# Power_Supply.net
KiCad netlist of a schematic drawn in Altium Designer
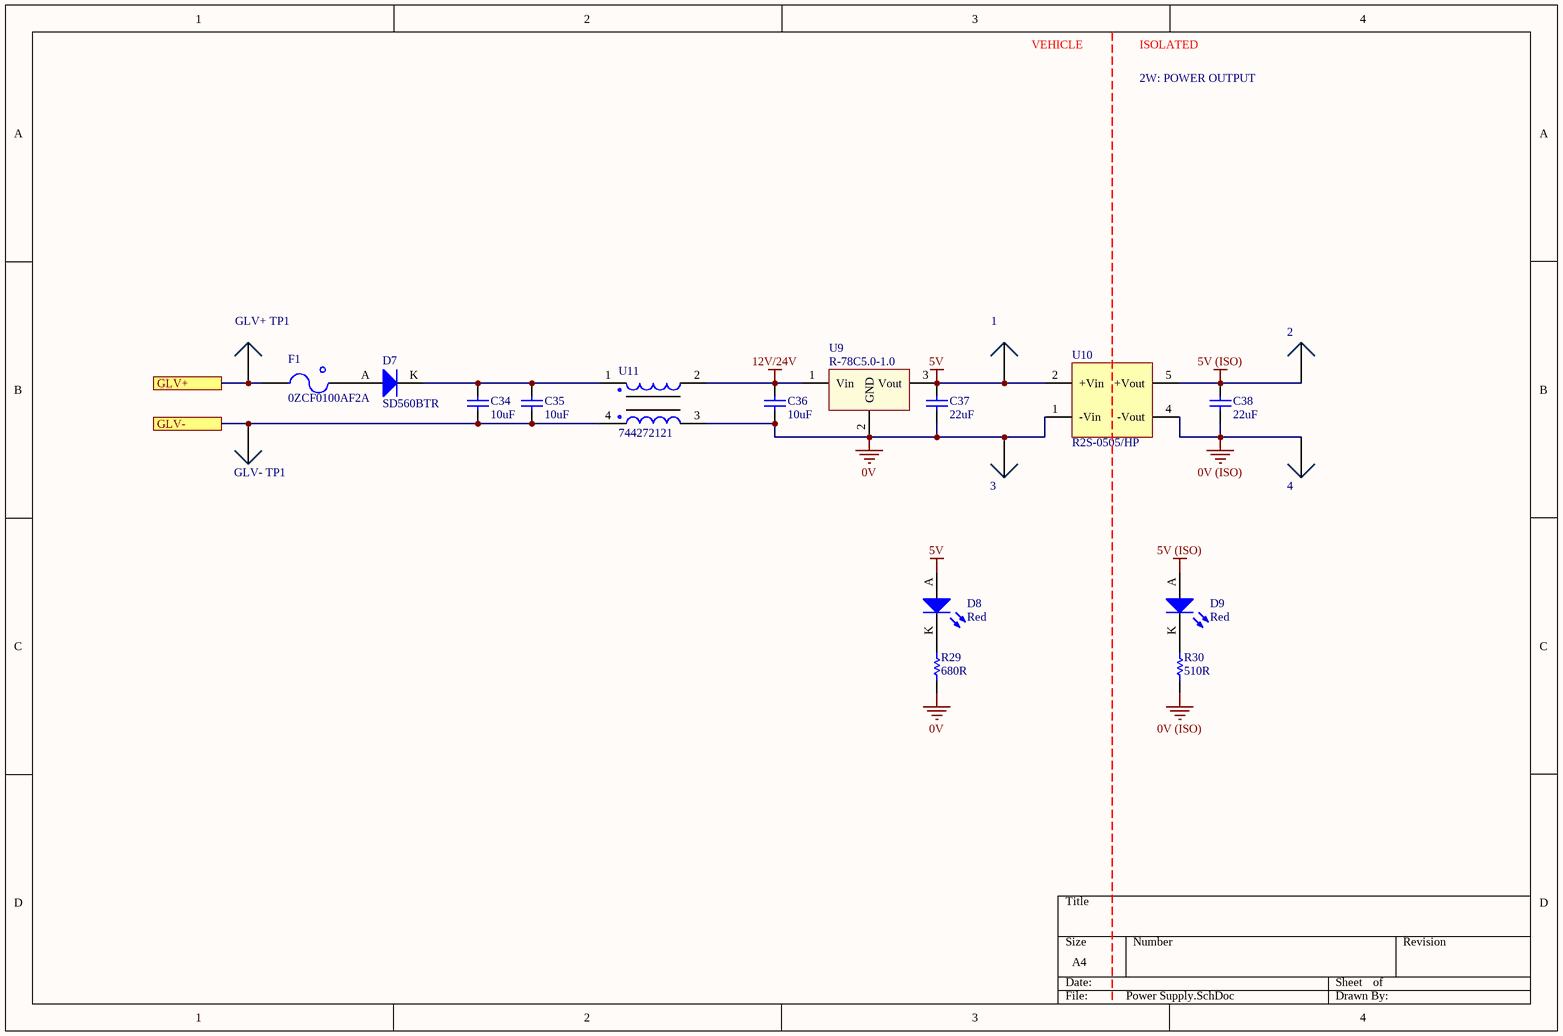
[diagram p0: Power Supply.SchDoc]

(export (version "E")
  (design (tool "Eeschema 10.0.6"))
  (components
    (comp (ref "1")
      (value "0mm")
      (footprint "SMD Test Point")
      (fields (field (name "PART NUMBER") "SMD Test Point") (field (name "CONTACT") "NA"))
      (libsource (lib "ts_20-standard-connectors") (part "Test Point"))
    )
    (comp (ref "2")
      (value "0mm")
      (footprint "SMD Test Point")
      (fields (field (name "PART NUMBER") "SMD Test Point") (field (name "CONTACT") "NA"))
      (libsource (lib "ts_20-standard-connectors") (part "Test Point"))
    )
    (comp (ref "3")
      (value "0mm")
      (footprint "SMD Test Point")
      (fields (field (name "PART NUMBER") "SMD Test Point") (field (name "CONTACT") "NA"))
      (libsource (lib "ts_20-standard-connectors") (part "Test Point"))
    )
    (comp (ref "4")
      (value "0mm")
      (footprint "SMD Test Point")
      (fields (field (name "PART NUMBER") "SMD Test Point") (field (name "CONTACT") "NA"))
      (libsource (lib "ts_20-standard-connectors") (part "Test Point"))
    )
    (comp (ref "C34")
      (value "10uF")
      (footprint "0805")
      (fields
        (field (name "PART NUMBER") "GRM21BR6YA106KE43L")
        (field (name "TOLERANCE") "10%")
        (field (name "MANUFACTURER") "muRata")
      )
      (libsource (lib "ts_20-standard-library") (part "Capacitor"))
    )
    (comp (ref "C35")
      (value "10uF")
      (footprint "0805")
      (fields
        (field (name "PART NUMBER") "GRM21BR6YA106KE43L")
        (field (name "TOLERANCE") "10%")
        (field (name "MANUFACTURER") "muRata")
      )
      (libsource (lib "ts_20-standard-library") (part "Capacitor"))
    )
    (comp (ref "C36")
      (value "10uF")
      (footprint "0805")
      (fields
        (field (name "PART NUMBER") "GRM21BR6YA106KE43L")
        (field (name "TOLERANCE") "10%")
        (field (name "MANUFACTURER") "muRata")
      )
      (libsource (lib "ts_20-standard-library") (part "Capacitor"))
    )
    (comp (ref "C37")
      (value "22uF")
      (footprint "1206")
      (fields
        (field (name "PART NUMBER") "CC1206MKX5R7BB226")
        (field (name "TOLERANCE") "20%")
        (field (name "MANUFACTURER") "YAGEO")
      )
      (libsource (lib "ts_20-standard-library") (part "Capacitor"))
    )
    (comp (ref "C38")
      (value "22uF")
      (footprint "1206")
      (fields
        (field (name "PART NUMBER") "CC1206MKX5R7BB226")
        (field (name "TOLERANCE") "20%")
        (field (name "MANUFACTURER") "YAGEO")
      )
      (libsource (lib "ts_20-standard-library") (part "Capacitor"))
    )
    (comp (ref "D7")
      (value "SD560BTR")
      (footprint "SMB Diode")
      (description "1.2V_F 600V 5A SMB")
      (fields
        (field (name "MANUFACTURER") "SMC Diode Solutions")
        (field (name "DIGIKEY PART NUMBER") "1655-1530-2-ND")
      )
      (libsource (lib "ts_20-standard-library") (part "Diode"))
    )
    (comp (ref "D8")
      (value "Red")
      (footprint "0805 LED")
      (description "Red LED Indication - Discrete 1.75V 0805 (2012 Metric)")
      (fields (field (name "PART NUMBER") "SML-210LTT86") (field (name "MANUFACTURER") "ROHM Semiconductor"))
      (libsource (lib "ts_20-standard-library") (part "LED"))
    )
    (comp (ref "D9")
      (value "Red")
      (footprint "0805 LED")
      (description "Red LED Indication - Discrete 1.75V 0805 (2012 Metric)")
      (fields (field (name "PART NUMBER") "SML-210LTT86") (field (name "MANUFACTURER") "ROHM Semiconductor"))
      (libsource (lib "ts_20-standard-library") (part "LED"))
    )
    (comp (ref "F1")
      (value "0ZCF0100AF2A")
      (footprint "2920")
      (description "PTC RESET FUSE 60V 1A 292")
      (fields
        (field (name "MANUFACTURER") "Littelfuse Inc.")
        (field (name "DIGIKEY PART NUMBER") "507-2070-1-ND")
      )
      (libsource (lib "ts_20-standard-library") (part "PTC Fuse"))
    )
    (comp (ref "GLV+ TP1")
      (value "0mm")
      (footprint "SMD Test Point")
      (fields (field (name "PART NUMBER") "SMD Test Point") (field (name "CONTACT") "NA"))
      (libsource (lib "ts_20-standard-connectors") (part "Test Point"))
    )
    (comp (ref "GLV- TP1")
      (value "0mm")
      (footprint "SMD Test Point")
      (fields (field (name "PART NUMBER") "SMD Test Point") (field (name "CONTACT") "NA"))
      (libsource (lib "ts_20-standard-connectors") (part "Test Point"))
    )
    (comp (ref "R29")
      (value "680R")
      (footprint "0805")
      (fields
        (field (name "PART NUMBER") "RC0805FR07680RL")
        (field (name "MANUFACTURER") "YAGEO")
        (field (name "TOLERANCE") "0.01")
      )
      (libsource (lib "ts_20-standard-library") (part "Resistor"))
    )
    (comp (ref "R30")
      (value "510R")
      (footprint "0805")
      (fields
        (field (name "PART NUMBER") "RC0805FR07510RL")
        (field (name "MANUFACTURER") "YAGEO")
        (field (name "TOLERANCE") "0.01")
      )
      (libsource (lib "ts_20-standard-library") (part "Resistor"))
    )
    (comp (ref "U9")
      (value "R-78C5.0-1.0")
      (footprint "RECOM 3-SIP")
      (description "CONV DC/DC 1A 5V OUT SIP VERT")
      (fields (field (name "MANUFACTURER") "Recom") (field (name "DIGIKEY PART NUMBER") "945-1395-5-ND"))
      (libsource (lib "ts_20-standard-library") (part "R-78C5.0-1.0"))
    )
    (comp (ref "U10")
      (value "R2S-0505/HP")
      (footprint "RECOM 8-SMD (5 Pin)")
      (description "Isolated Module DC DC Converter 1 Output 3.3V 606mA 4.5V - 5.5V Input")
      (fields (field (name "MANUFACTURER") "Recom") (field (name "DIGIKEY PART NUMBER") "945-1764-5-ND"))
      (libsource (lib "ts_20-standard-library") (part "R2S-0505/HP"))
    )
    (comp (ref "U11")
      (value "744272121")
      (footprint "INDC3216")
      (description "120µH @ 100kHz 2 Line Common Mode Choke Surface Mount 460 Ohms @ 30MHz 2.5A DCR 25mOhm")
      (fields
        (field (name "MANUFACTURER") "Wurth Electronics Inc")
        (field (name "DIGIKEY PART NUMBER") "732-1489-1-ND")
      )
      (libsource (lib "ts_20-standard-library") (part "744272121"))
    )
  )
  (nets
    (net (code "1") (name "/GLV+") (class "Default")
      (node (ref "F1") (pin "1") (pinfunction "1_1") (pintype "passive"))
      (node (ref "GLV+ TP1") (pin "1") (pinfunction "1_1") (pintype "passive"))
    )
    (net (code "2") (name "/GLV-") (class "Default")
      (node (ref "C34") (pin "1") (pinfunction "1_1") (pintype "passive"))
      (node (ref "C35") (pin "1") (pinfunction "1_1") (pintype "passive"))
      (node (ref "GLV- TP1") (pin "1") (pinfunction "1_1") (pintype "passive"))
      (node (ref "U11") (pin "4") (pinfunction "4_4") (pintype "passive"))
    )
    (net (code "3") (name "0V") (class "Default")
      (node (ref "3") (pin "1") (pinfunction "1_1") (pintype "passive"))
      (node (ref "C36") (pin "1") (pinfunction "1_1") (pintype "passive"))
      (node (ref "C37") (pin "1") (pinfunction "1_1") (pintype "passive"))
      (node (ref "R29") (pin "1") (pinfunction "1_1") (pintype "passive"))
      (node (ref "U10") (pin "1") (pinfunction "-Vin_1") (pintype "power_in"))
      (node (ref "U11") (pin "3") (pinfunction "3_3") (pintype "power_in"))
      (node (ref "U9") (pin "2") (pinfunction "GND_2") (pintype "passive"))
    )
    (net (code "4") (name "0V (ISO)") (class "Default")
      (node (ref "4") (pin "1") (pinfunction "1_1") (pintype "passive"))
      (node (ref "C38") (pin "1") (pinfunction "1_1") (pintype "passive"))
      (node (ref "R30") (pin "1") (pinfunction "1_1") (pintype "passive"))
      (node (ref "U10") (pin "4") (pinfunction "-Vout_4") (pintype "power_in"))
    )
    (net (code "5") (name "5V") (class "Default")
      (node (ref "1") (pin "1") (pinfunction "1_1") (pintype "passive"))
      (node (ref "C37") (pin "2") (pinfunction "2_2") (pintype "passive"))
      (node (ref "D8") (pin "A") (pinfunction "A_A") (pintype "passive"))
      (node (ref "U10") (pin "2") (pinfunction "+Vin_2") (pintype "power_in"))
      (node (ref "U9") (pin "3") (pinfunction "Vout_3") (pintype "passive"))
    )
    (net (code "6") (name "5V (ISO)") (class "Default")
      (node (ref "2") (pin "1") (pinfunction "1_1") (pintype "passive"))
      (node (ref "C38") (pin "2") (pinfunction "2_2") (pintype "passive"))
      (node (ref "D9") (pin "A") (pinfunction "A_A") (pintype "passive"))
      (node (ref "U10") (pin "5") (pinfunction "+Vout_5") (pintype "power_in"))
    )
    (net (code "7") (name "12V{slash}24V") (class "Default")
      (node (ref "C36") (pin "2") (pinfunction "2_2") (pintype "passive"))
      (node (ref "U11") (pin "2") (pinfunction "2_2") (pintype "passive"))
      (node (ref "U9") (pin "1") (pinfunction "Vin_1") (pintype "passive"))
    )
    (net (code "8") (name "Net-(C34-Pad2)") (class "Default")
      (node (ref "C34") (pin "2") (pinfunction "2_2") (pintype "passive"))
      (node (ref "C35") (pin "2") (pinfunction "2_2") (pintype "passive"))
      (node (ref "D7") (pin "K") (pinfunction "K_K") (pintype "passive"))
      (node (ref "U11") (pin "1") (pinfunction "1_1") (pintype "passive"))
    )
    (net (code "9") (name "Net-(D7-PadA)") (class "Default")
      (node (ref "D7") (pin "A") (pinfunction "A_A") (pintype "passive"))
      (node (ref "F1") (pin "2") (pinfunction "2_2") (pintype "passive"))
    )
    (net (code "10") (name "Net-(D8-PadK)") (class "Default")
      (node (ref "D8") (pin "K") (pinfunction "K_K") (pintype "passive"))
      (node (ref "R29") (pin "2") (pinfunction "2_2") (pintype "passive"))
    )
    (net (code "11") (name "Net-(D9-PadK)") (class "Default")
      (node (ref "D9") (pin "K") (pinfunction "K_K") (pintype "passive"))
      (node (ref "R30") (pin "2") (pinfunction "2_2") (pintype "passive"))
    )
  )
)
